# DSPCONN_12-15.net
KiCad netlist of a schematic drawn in Altium Designer
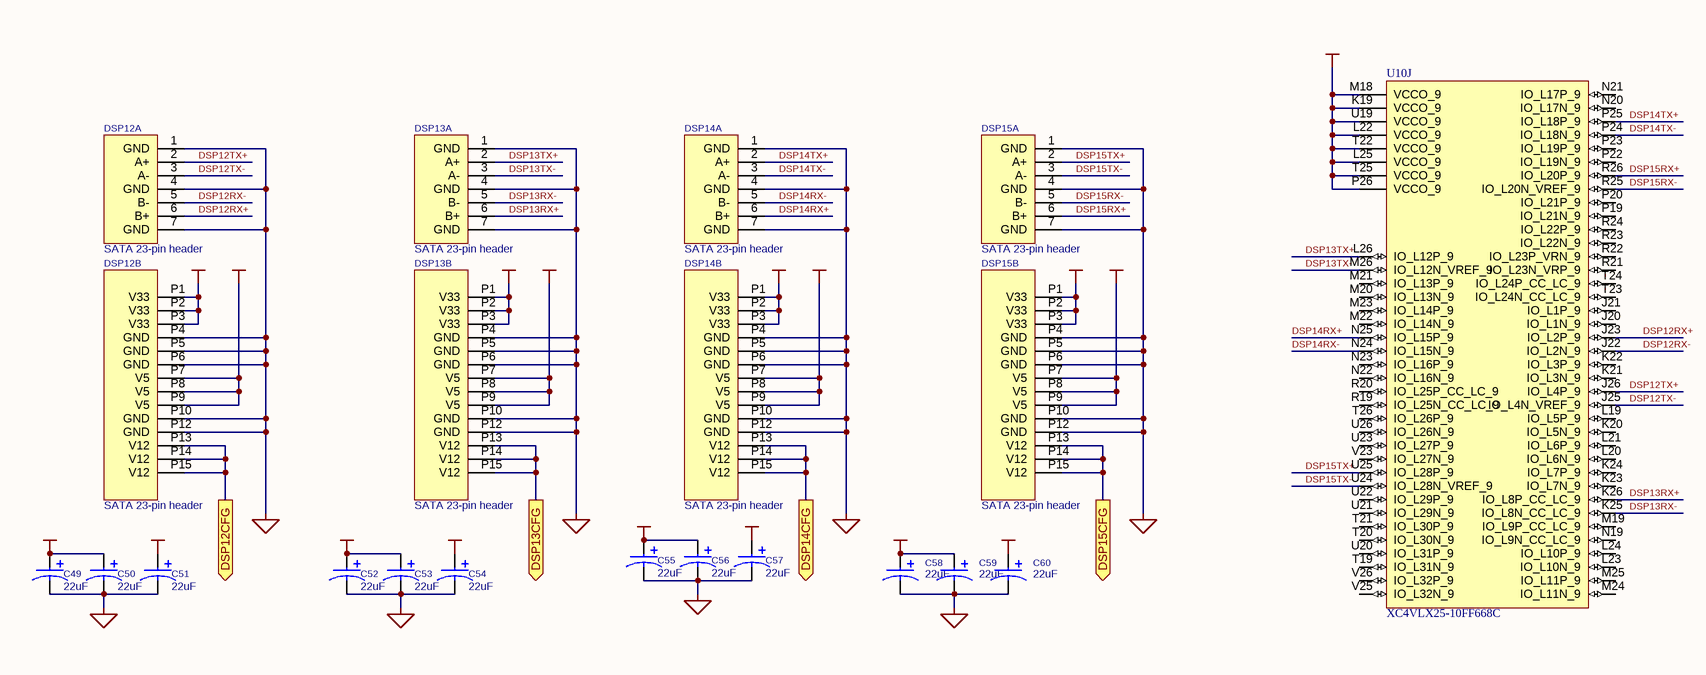
[diagram p0: DSPCONN.12-15.SCHDOC]

(export (version "E")
  (design (tool "Eeschema 10.0.6"))
  (components
    (comp (ref "C49")
      (value "22uF")
      (footprint "6032")
      (description "Standard Capacitor")
      (fields (field (name "Comment") "POLCAP2"))
      (libsource (lib "parts") (part "POLCAP2"))
    )
    (comp (ref "C50")
      (value "22uF")
      (footprint "6032")
      (description "Standard Capacitor")
      (fields (field (name "Comment") "POLCAP2"))
      (libsource (lib "parts") (part "POLCAP2"))
    )
    (comp (ref "C51")
      (value "22uF")
      (footprint "6032")
      (description "Standard Capacitor")
      (fields (field (name "Comment") "POLCAP2"))
      (libsource (lib "parts") (part "POLCAP2"))
    )
    (comp (ref "C52")
      (value "22uF")
      (footprint "6032")
      (description "Standard Capacitor")
      (fields (field (name "Comment") "POLCAP2"))
      (libsource (lib "parts") (part "POLCAP2"))
    )
    (comp (ref "C53")
      (value "22uF")
      (footprint "6032")
      (description "Standard Capacitor")
      (fields (field (name "Comment") "POLCAP2"))
      (libsource (lib "parts") (part "POLCAP2"))
    )
    (comp (ref "C54")
      (value "22uF")
      (footprint "6032")
      (description "Standard Capacitor")
      (fields (field (name "Comment") "POLCAP2"))
      (libsource (lib "parts") (part "POLCAP2"))
    )
    (comp (ref "C55")
      (value "22uF")
      (footprint "6032")
      (description "Standard Capacitor")
      (fields (field (name "Comment") "POLCAP2"))
      (libsource (lib "parts") (part "POLCAP2"))
    )
    (comp (ref "C56")
      (value "22uF")
      (footprint "6032")
      (description "Standard Capacitor")
      (fields (field (name "Comment") "POLCAP2"))
      (libsource (lib "parts") (part "POLCAP2"))
    )
    (comp (ref "C57")
      (value "22uF")
      (footprint "6032")
      (description "Standard Capacitor")
      (fields (field (name "Comment") "POLCAP2"))
      (libsource (lib "parts") (part "POLCAP2"))
    )
    (comp (ref "C58")
      (value "22uF")
      (footprint "6032")
      (description "Standard Capacitor")
      (fields (field (name "Comment") "POLCAP2"))
      (libsource (lib "parts") (part "POLCAP2"))
    )
    (comp (ref "C59")
      (value "22uF")
      (footprint "6032")
      (description "Standard Capacitor")
      (fields (field (name "Comment") "POLCAP2"))
      (libsource (lib "parts") (part "POLCAP2"))
    )
    (comp (ref "C60")
      (value "22uF")
      (footprint "6032")
      (description "Standard Capacitor")
      (fields (field (name "Comment") "POLCAP2"))
      (libsource (lib "parts") (part "POLCAP2"))
    )
    (comp (ref "DSP12")
      (value "SATA 23-pin header")
      (footprint "MOLEX 87713-1001")
      (libsource (lib "parts") (part "SATA-23"))
    )
    (comp (ref "DSP13")
      (value "SATA 23-pin header")
      (footprint "MOLEX 87713-1001")
      (libsource (lib "parts") (part "SATA-23"))
    )
    (comp (ref "DSP14")
      (value "SATA 23-pin header")
      (footprint "MOLEX 87713-1001")
      (libsource (lib "parts") (part "SATA-23"))
    )
    (comp (ref "DSP15")
      (value "SATA 23-pin header")
      (footprint "MOLEX 87713-1001")
      (libsource (lib "parts") (part "SATA-23"))
    )
    (comp (ref "U10")
      (value "XC4VLX25-10FF668C")
      (footprint "Xilinx FF668")
      (description "Xilinx Virtex-4")
      (libsource (lib "parts") (part "XC4VLX25-10FF668C"))
    )
  )
  (nets
    (net (code "1") (name "+2.5VCC") (class "Default")
      (node (ref "U10") (pin "K19") (pinfunction "VCCO_9_K19") (pintype "power_in"))
      (node (ref "U10") (pin "L22") (pinfunction "VCCO_9_L22") (pintype "power_in"))
      (node (ref "U10") (pin "L25") (pinfunction "VCCO_9_L25") (pintype "power_in"))
      (node (ref "U10") (pin "M18") (pinfunction "VCCO_9_M18") (pintype "power_in"))
      (node (ref "U10") (pin "P26") (pinfunction "VCCO_9_P26") (pintype "power_in"))
      (node (ref "U10") (pin "T22") (pinfunction "VCCO_9_T22") (pintype "power_in"))
      (node (ref "U10") (pin "T25") (pinfunction "VCCO_9_T25") (pintype "power_in"))
      (node (ref "U10") (pin "U19") (pinfunction "VCCO_9_U19") (pintype "power_in"))
    )
    (net (code "2") (name "+5VCC") (class "Default")
      (node (ref "C51") (pin "1") (pintype "passive"))
      (node (ref "C54") (pin "1") (pintype "passive"))
      (node (ref "C57") (pin "1") (pintype "passive"))
      (node (ref "C60") (pin "1") (pintype "passive"))
      (node (ref "DSP12") (pin "P7") (pinfunction "V5_P7") (pintype "passive"))
      (node (ref "DSP12") (pin "P8") (pinfunction "V5_P8") (pintype "passive"))
      (node (ref "DSP12") (pin "P9") (pinfunction "V5_P9") (pintype "passive"))
      (node (ref "DSP13") (pin "P7") (pinfunction "V5_P7") (pintype "passive"))
      (node (ref "DSP13") (pin "P8") (pinfunction "V5_P8") (pintype "passive"))
      (node (ref "DSP13") (pin "P9") (pinfunction "V5_P9") (pintype "passive"))
      (node (ref "DSP14") (pin "P7") (pinfunction "V5_P7") (pintype "passive"))
      (node (ref "DSP14") (pin "P8") (pinfunction "V5_P8") (pintype "passive"))
      (node (ref "DSP14") (pin "P9") (pinfunction "V5_P9") (pintype "passive"))
      (node (ref "DSP15") (pin "P7") (pinfunction "V5_P7") (pintype "passive"))
      (node (ref "DSP15") (pin "P8") (pinfunction "V5_P8") (pintype "passive"))
      (node (ref "DSP15") (pin "P9") (pinfunction "V5_P9") (pintype "passive"))
    )
    (net (code "3") (name "/DSP12CFG") (class "Default")
      (node (ref "DSP12") (pin "P13") (pinfunction "V12_P13") (pintype "passive"))
      (node (ref "DSP12") (pin "P14") (pinfunction "V12_P14") (pintype "passive"))
      (node (ref "DSP12") (pin "P15") (pinfunction "V12_P15") (pintype "passive"))
    )
    (net (code "4") (name "/DSP12RX+") (class "Default")
      (node (ref "DSP12") (pin "6") (pinfunction "B+_6") (pintype "passive"))
      (node (ref "U10") (pin "J23") (pinfunction "IO_L2P_9_J23") (pintype "bidirectional"))
    )
    (net (code "5") (name "/DSP12RX-") (class "Default")
      (node (ref "DSP12") (pin "5") (pinfunction "B-_5") (pintype "passive"))
      (node (ref "U10") (pin "J22") (pinfunction "IO_L2N_9_J22") (pintype "bidirectional"))
    )
    (net (code "6") (name "/DSP12TX+") (class "Default")
      (node (ref "DSP12") (pin "2") (pinfunction "A+_2") (pintype "passive"))
      (node (ref "U10") (pin "J26") (pinfunction "IO_L4P_9_J26") (pintype "bidirectional"))
    )
    (net (code "7") (name "/DSP12TX-") (class "Default")
      (node (ref "DSP12") (pin "3") (pinfunction "A-_3") (pintype "passive"))
      (node (ref "U10") (pin "J25") (pinfunction "IO_L4N_VREF_9_J25") (pintype "bidirectional"))
    )
    (net (code "8") (name "/DSP13CFG") (class "Default")
      (node (ref "DSP13") (pin "P13") (pinfunction "V12_P13") (pintype "passive"))
      (node (ref "DSP13") (pin "P14") (pinfunction "V12_P14") (pintype "passive"))
      (node (ref "DSP13") (pin "P15") (pinfunction "V12_P15") (pintype "passive"))
    )
    (net (code "9") (name "/DSP13RX+") (class "Default")
      (node (ref "DSP13") (pin "6") (pinfunction "B+_6") (pintype "passive"))
      (node (ref "U10") (pin "K26") (pinfunction "IO_L8P_CC_LC_9_K26") (pintype "bidirectional"))
    )
    (net (code "10") (name "/DSP13RX-") (class "Default")
      (node (ref "DSP13") (pin "5") (pinfunction "B-_5") (pintype "passive"))
      (node (ref "U10") (pin "K25") (pinfunction "IO_L8N_CC_LC_9_K25") (pintype "bidirectional"))
    )
    (net (code "11") (name "/DSP13TX+") (class "Default")
      (node (ref "DSP13") (pin "2") (pinfunction "A+_2") (pintype "passive"))
      (node (ref "U10") (pin "L26") (pinfunction "IO_L12P_9_L26") (pintype "bidirectional"))
    )
    (net (code "12") (name "/DSP13TX-") (class "Default")
      (node (ref "DSP13") (pin "3") (pinfunction "A-_3") (pintype "passive"))
      (node (ref "U10") (pin "M26") (pinfunction "IO_L12N_VREF_9_M26") (pintype "bidirectional"))
    )
    (net (code "13") (name "/DSP14CFG") (class "Default")
      (node (ref "DSP14") (pin "P13") (pinfunction "V12_P13") (pintype "passive"))
      (node (ref "DSP14") (pin "P14") (pinfunction "V12_P14") (pintype "passive"))
      (node (ref "DSP14") (pin "P15") (pinfunction "V12_P15") (pintype "passive"))
    )
    (net (code "14") (name "/DSP14RX+") (class "Default")
      (node (ref "DSP14") (pin "6") (pinfunction "B+_6") (pintype "passive"))
      (node (ref "U10") (pin "N25") (pinfunction "IO_L15P_9_N25") (pintype "bidirectional"))
    )
    (net (code "15") (name "/DSP14RX-") (class "Default")
      (node (ref "DSP14") (pin "5") (pinfunction "B-_5") (pintype "passive"))
      (node (ref "U10") (pin "N24") (pinfunction "IO_L15N_9_N24") (pintype "bidirectional"))
    )
    (net (code "16") (name "/DSP14TX+") (class "Default")
      (node (ref "DSP14") (pin "2") (pinfunction "A+_2") (pintype "passive"))
      (node (ref "U10") (pin "P25") (pinfunction "IO_L18P_9_P25") (pintype "bidirectional"))
    )
    (net (code "17") (name "/DSP14TX-") (class "Default")
      (node (ref "DSP14") (pin "3") (pinfunction "A-_3") (pintype "passive"))
      (node (ref "U10") (pin "P24") (pinfunction "IO_L18N_9_P24") (pintype "bidirectional"))
    )
    (net (code "18") (name "/DSP15CFG") (class "Default")
      (node (ref "DSP15") (pin "P13") (pinfunction "V12_P13") (pintype "passive"))
      (node (ref "DSP15") (pin "P14") (pinfunction "V12_P14") (pintype "passive"))
      (node (ref "DSP15") (pin "P15") (pinfunction "V12_P15") (pintype "passive"))
    )
    (net (code "19") (name "/DSP15RX+") (class "Default")
      (node (ref "DSP15") (pin "6") (pinfunction "B+_6") (pintype "passive"))
      (node (ref "U10") (pin "R26") (pinfunction "IO_L20P_9_R26") (pintype "bidirectional"))
    )
    (net (code "20") (name "/DSP15RX-") (class "Default")
      (node (ref "DSP15") (pin "5") (pinfunction "B-_5") (pintype "passive"))
      (node (ref "U10") (pin "R25") (pinfunction "IO_L20N_VREF_9_R25") (pintype "bidirectional"))
    )
    (net (code "21") (name "/DSP15TX+") (class "Default")
      (node (ref "DSP15") (pin "2") (pinfunction "A+_2") (pintype "passive"))
      (node (ref "U10") (pin "U25") (pinfunction "IO_L28P_9_U25") (pintype "bidirectional"))
    )
    (net (code "22") (name "/DSP15TX-") (class "Default")
      (node (ref "DSP15") (pin "3") (pinfunction "A-_3") (pintype "passive"))
      (node (ref "U10") (pin "U24") (pinfunction "IO_L28N_VREF_9_U24") (pintype "bidirectional"))
    )
    (net (code "23") (name "GND") (class "Default")
      (node (ref "C49") (pin "2") (pintype "passive"))
      (node (ref "C50") (pin "2") (pintype "passive"))
      (node (ref "C51") (pin "2") (pintype "passive"))
      (node (ref "C52") (pin "2") (pintype "passive"))
      (node (ref "C53") (pin "2") (pintype "passive"))
      (node (ref "C54") (pin "2") (pintype "passive"))
      (node (ref "C55") (pin "2") (pintype "passive"))
      (node (ref "C56") (pin "2") (pintype "passive"))
      (node (ref "C57") (pin "2") (pintype "passive"))
      (node (ref "C58") (pin "2") (pintype "passive"))
      (node (ref "C59") (pin "2") (pintype "passive"))
      (node (ref "C60") (pin "2") (pintype "passive"))
      (node (ref "DSP12") (pin "1") (pinfunction "GND_1") (pintype "passive"))
      (node (ref "DSP12") (pin "4") (pinfunction "GND_4") (pintype "passive"))
      (node (ref "DSP12") (pin "7") (pinfunction "GND_7") (pintype "passive"))
      (node (ref "DSP12") (pin "P10") (pinfunction "GND_P10") (pintype "passive"))
      (node (ref "DSP12") (pin "P12") (pinfunction "GND_P12") (pintype "passive"))
      (node (ref "DSP12") (pin "P4") (pinfunction "GND_P4") (pintype "passive"))
      (node (ref "DSP12") (pin "P5") (pinfunction "GND_P5") (pintype "passive"))
      (node (ref "DSP12") (pin "P6") (pinfunction "GND_P6") (pintype "passive"))
      (node (ref "DSP13") (pin "1") (pinfunction "GND_1") (pintype "passive"))
      (node (ref "DSP13") (pin "4") (pinfunction "GND_4") (pintype "passive"))
      (node (ref "DSP13") (pin "7") (pinfunction "GND_7") (pintype "passive"))
      (node (ref "DSP13") (pin "P10") (pinfunction "GND_P10") (pintype "passive"))
      (node (ref "DSP13") (pin "P12") (pinfunction "GND_P12") (pintype "passive"))
      (node (ref "DSP13") (pin "P4") (pinfunction "GND_P4") (pintype "passive"))
      (node (ref "DSP13") (pin "P5") (pinfunction "GND_P5") (pintype "passive"))
      (node (ref "DSP13") (pin "P6") (pinfunction "GND_P6") (pintype "passive"))
      (node (ref "DSP14") (pin "1") (pinfunction "GND_1") (pintype "passive"))
      (node (ref "DSP14") (pin "4") (pinfunction "GND_4") (pintype "passive"))
      (node (ref "DSP14") (pin "7") (pinfunction "GND_7") (pintype "passive"))
      (node (ref "DSP14") (pin "P10") (pinfunction "GND_P10") (pintype "passive"))
      (node (ref "DSP14") (pin "P12") (pinfunction "GND_P12") (pintype "passive"))
      (node (ref "DSP14") (pin "P4") (pinfunction "GND_P4") (pintype "passive"))
      (node (ref "DSP14") (pin "P5") (pinfunction "GND_P5") (pintype "passive"))
      (node (ref "DSP14") (pin "P6") (pinfunction "GND_P6") (pintype "passive"))
      (node (ref "DSP15") (pin "1") (pinfunction "GND_1") (pintype "passive"))
      (node (ref "DSP15") (pin "4") (pinfunction "GND_4") (pintype "passive"))
      (node (ref "DSP15") (pin "7") (pinfunction "GND_7") (pintype "passive"))
      (node (ref "DSP15") (pin "P10") (pinfunction "GND_P10") (pintype "passive"))
      (node (ref "DSP15") (pin "P12") (pinfunction "GND_P12") (pintype "passive"))
      (node (ref "DSP15") (pin "P4") (pinfunction "GND_P4") (pintype "passive"))
      (node (ref "DSP15") (pin "P5") (pinfunction "GND_P5") (pintype "passive"))
      (node (ref "DSP15") (pin "P6") (pinfunction "GND_P6") (pintype "passive"))
    )
    (net (code "24") (name "VCC2") (class "Default")
      (node (ref "C49") (pin "1") (pintype "passive"))
      (node (ref "C50") (pin "1") (pintype "passive"))
      (node (ref "C52") (pin "1") (pintype "passive"))
      (node (ref "C53") (pin "1") (pintype "passive"))
      (node (ref "C55") (pin "1") (pintype "passive"))
      (node (ref "C56") (pin "1") (pintype "passive"))
      (node (ref "C58") (pin "1") (pintype "passive"))
      (node (ref "C59") (pin "1") (pintype "passive"))
      (node (ref "DSP12") (pin "P1") (pinfunction "V33_P1") (pintype "passive"))
      (node (ref "DSP12") (pin "P2") (pinfunction "V33_P2") (pintype "passive"))
      (node (ref "DSP12") (pin "P3") (pinfunction "V33_P3") (pintype "passive"))
      (node (ref "DSP13") (pin "P1") (pinfunction "V33_P1") (pintype "passive"))
      (node (ref "DSP13") (pin "P2") (pinfunction "V33_P2") (pintype "passive"))
      (node (ref "DSP13") (pin "P3") (pinfunction "V33_P3") (pintype "passive"))
      (node (ref "DSP14") (pin "P1") (pinfunction "V33_P1") (pintype "passive"))
      (node (ref "DSP14") (pin "P2") (pinfunction "V33_P2") (pintype "passive"))
      (node (ref "DSP14") (pin "P3") (pinfunction "V33_P3") (pintype "passive"))
      (node (ref "DSP15") (pin "P1") (pinfunction "V33_P1") (pintype "passive"))
      (node (ref "DSP15") (pin "P2") (pinfunction "V33_P2") (pintype "passive"))
      (node (ref "DSP15") (pin "P3") (pinfunction "V33_P3") (pintype "passive"))
    )
    (net (code "25") (name "unconnected-(U10J-IO_L1N_9-PadJ20)") (class "Default")
      (node (ref "U10") (pin "J20") (pinfunction "IO_L1N_9_J20") (pintype "bidirectional"))
    )
    (net (code "26") (name "unconnected-(U10J-IO_L1P_9-PadJ21)") (class "Default")
      (node (ref "U10") (pin "J21") (pinfunction "IO_L1P_9_J21") (pintype "bidirectional"))
    )
    (net (code "27") (name "unconnected-(U10J-IO_L3N_9-PadK21)") (class "Default")
      (node (ref "U10") (pin "K21") (pinfunction "IO_L3N_9_K21") (pintype "bidirectional"))
    )
    (net (code "28") (name "unconnected-(U10J-IO_L3P_9-PadK22)") (class "Default")
      (node (ref "U10") (pin "K22") (pinfunction "IO_L3P_9_K22") (pintype "bidirectional"))
    )
    (net (code "29") (name "unconnected-(U10J-IO_L5N_9-PadK20)") (class "Default")
      (node (ref "U10") (pin "K20") (pinfunction "IO_L5N_9_K20") (pintype "bidirectional"))
    )
    (net (code "30") (name "unconnected-(U10J-IO_L5P_9-PadL19)") (class "Default")
      (node (ref "U10") (pin "L19") (pinfunction "IO_L5P_9_L19") (pintype "bidirectional"))
    )
    (net (code "31") (name "unconnected-(U10J-IO_L6N_9-PadL20)") (class "Default")
      (node (ref "U10") (pin "L20") (pinfunction "IO_L6N_9_L20") (pintype "bidirectional"))
    )
    (net (code "32") (name "unconnected-(U10J-IO_L6P_9-PadL21)") (class "Default")
      (node (ref "U10") (pin "L21") (pinfunction "IO_L6P_9_L21") (pintype "bidirectional"))
    )
    (net (code "33") (name "unconnected-(U10J-IO_L7N_9-PadK23)") (class "Default")
      (node (ref "U10") (pin "K23") (pinfunction "IO_L7N_9_K23") (pintype "bidirectional"))
    )
    (net (code "34") (name "unconnected-(U10J-IO_L7P_9-PadK24)") (class "Default")
      (node (ref "U10") (pin "K24") (pinfunction "IO_L7P_9_K24") (pintype "bidirectional"))
    )
    (net (code "35") (name "unconnected-(U10J-IO_L9N_CC_LC_9-PadN19)") (class "Default")
      (node (ref "U10") (pin "N19") (pinfunction "IO_L9N_CC_LC_9_N19") (pintype "bidirectional"))
    )
    (net (code "36") (name "unconnected-(U10J-IO_L9P_CC_LC_9-PadM19)") (class "Default")
      (node (ref "U10") (pin "M19") (pinfunction "IO_L9P_CC_LC_9_M19") (pintype "bidirectional"))
    )
    (net (code "37") (name "unconnected-(U10J-IO_L10N_9-PadL23)") (class "Default")
      (node (ref "U10") (pin "L23") (pinfunction "IO_L10N_9_L23") (pintype "bidirectional"))
    )
    (net (code "38") (name "unconnected-(U10J-IO_L10P_9-PadL24)") (class "Default")
      (node (ref "U10") (pin "L24") (pinfunction "IO_L10P_9_L24") (pintype "bidirectional"))
    )
    (net (code "39") (name "unconnected-(U10J-IO_L11N_9-PadM24)") (class "Default")
      (node (ref "U10") (pin "M24") (pinfunction "IO_L11N_9_M24") (pintype "bidirectional"))
    )
    (net (code "40") (name "unconnected-(U10J-IO_L11P_9-PadM25)") (class "Default")
      (node (ref "U10") (pin "M25") (pinfunction "IO_L11P_9_M25") (pintype "bidirectional"))
    )
    (net (code "41") (name "unconnected-(U10J-IO_L13N_9-PadM20)") (class "Default")
      (node (ref "U10") (pin "M20") (pinfunction "IO_L13N_9_M20") (pintype "bidirectional"))
    )
    (net (code "42") (name "unconnected-(U10J-IO_L13P_9-PadM21)") (class "Default")
      (node (ref "U10") (pin "M21") (pinfunction "IO_L13P_9_M21") (pintype "bidirectional"))
    )
    (net (code "43") (name "unconnected-(U10J-IO_L14N_9-PadM22)") (class "Default")
      (node (ref "U10") (pin "M22") (pinfunction "IO_L14N_9_M22") (pintype "bidirectional"))
    )
    (net (code "44") (name "unconnected-(U10J-IO_L14P_9-PadM23)") (class "Default")
      (node (ref "U10") (pin "M23") (pinfunction "IO_L14P_9_M23") (pintype "bidirectional"))
    )
    (net (code "45") (name "unconnected-(U10J-IO_L16N_9-PadN22)") (class "Default")
      (node (ref "U10") (pin "N22") (pinfunction "IO_L16N_9_N22") (pintype "bidirectional"))
    )
    (net (code "46") (name "unconnected-(U10J-IO_L16P_9-PadN23)") (class "Default")
      (node (ref "U10") (pin "N23") (pinfunction "IO_L16P_9_N23") (pintype "bidirectional"))
    )
    (net (code "47") (name "unconnected-(U10J-IO_L17N_9-PadN20)") (class "Default")
      (node (ref "U10") (pin "N20") (pinfunction "IO_L17N_9_N20") (pintype "bidirectional"))
    )
    (net (code "48") (name "unconnected-(U10J-IO_L17P_9-PadN21)") (class "Default")
      (node (ref "U10") (pin "N21") (pinfunction "IO_L17P_9_N21") (pintype "bidirectional"))
    )
    (net (code "49") (name "unconnected-(U10J-IO_L19N_9-PadP22)") (class "Default")
      (node (ref "U10") (pin "P22") (pinfunction "IO_L19N_9_P22") (pintype "bidirectional"))
    )
    (net (code "50") (name "unconnected-(U10J-IO_L19P_9-PadP23)") (class "Default")
      (node (ref "U10") (pin "P23") (pinfunction "IO_L19P_9_P23") (pintype "bidirectional"))
    )
    (net (code "51") (name "unconnected-(U10J-IO_L21N_9-PadP19)") (class "Default")
      (node (ref "U10") (pin "P19") (pinfunction "IO_L21N_9_P19") (pintype "bidirectional"))
    )
    (net (code "52") (name "unconnected-(U10J-IO_L21P_9-PadP20)") (class "Default")
      (node (ref "U10") (pin "P20") (pinfunction "IO_L21P_9_P20") (pintype "bidirectional"))
    )
    (net (code "53") (name "unconnected-(U10J-IO_L22N_9-PadR23)") (class "Default")
      (node (ref "U10") (pin "R23") (pinfunction "IO_L22N_9_R23") (pintype "bidirectional"))
    )
    (net (code "54") (name "unconnected-(U10J-IO_L22P_9-PadR24)") (class "Default")
      (node (ref "U10") (pin "R24") (pinfunction "IO_L22P_9_R24") (pintype "bidirectional"))
    )
    (net (code "55") (name "unconnected-(U10J-IO_L23N_VRP_9-PadR21)") (class "Default")
      (node (ref "U10") (pin "R21") (pinfunction "IO_L23N_VRP_9_R21") (pintype "bidirectional"))
    )
    (net (code "56") (name "unconnected-(U10J-IO_L23P_VRN_9-PadR22)") (class "Default")
      (node (ref "U10") (pin "R22") (pinfunction "IO_L23P_VRN_9_R22") (pintype "bidirectional"))
    )
    (net (code "57") (name "unconnected-(U10J-IO_L24N_CC_LC_9-PadT23)") (class "Default")
      (node (ref "U10") (pin "T23") (pinfunction "IO_L24N_CC_LC_9_T23") (pintype "bidirectional"))
    )
    (net (code "58") (name "unconnected-(U10J-IO_L24P_CC_LC_9-PadT24)") (class "Default")
      (node (ref "U10") (pin "T24") (pinfunction "IO_L24P_CC_LC_9_T24") (pintype "bidirectional"))
    )
    (net (code "59") (name "unconnected-(U10J-IO_L25N_CC_LC_9-PadR19)") (class "Default")
      (node (ref "U10") (pin "R19") (pinfunction "IO_L25N_CC_LC_9_R19") (pintype "bidirectional"))
    )
    (net (code "60") (name "unconnected-(U10J-IO_L25P_CC_LC_9-PadR20)") (class "Default")
      (node (ref "U10") (pin "R20") (pinfunction "IO_L25P_CC_LC_9_R20") (pintype "bidirectional"))
    )
    (net (code "61") (name "unconnected-(U10J-IO_L26N_9-PadU26)") (class "Default")
      (node (ref "U10") (pin "U26") (pinfunction "IO_L26N_9_U26") (pintype "bidirectional"))
    )
    (net (code "62") (name "unconnected-(U10J-IO_L26P_9-PadT26)") (class "Default")
      (node (ref "U10") (pin "T26") (pinfunction "IO_L26P_9_T26") (pintype "bidirectional"))
    )
    (net (code "63") (name "unconnected-(U10J-IO_L27N_9-PadV23)") (class "Default")
      (node (ref "U10") (pin "V23") (pinfunction "IO_L27N_9_V23") (pintype "bidirectional"))
    )
    (net (code "64") (name "unconnected-(U10J-IO_L27P_9-PadU23)") (class "Default")
      (node (ref "U10") (pin "U23") (pinfunction "IO_L27P_9_U23") (pintype "bidirectional"))
    )
    (net (code "65") (name "unconnected-(U10J-IO_L29N_9-PadU21)") (class "Default")
      (node (ref "U10") (pin "U21") (pinfunction "IO_L29N_9_U21") (pintype "bidirectional"))
    )
    (net (code "66") (name "unconnected-(U10J-IO_L29P_9-PadU22)") (class "Default")
      (node (ref "U10") (pin "U22") (pinfunction "IO_L29P_9_U22") (pintype "bidirectional"))
    )
    (net (code "67") (name "unconnected-(U10J-IO_L30N_9-PadT20)") (class "Default")
      (node (ref "U10") (pin "T20") (pinfunction "IO_L30N_9_T20") (pintype "bidirectional"))
    )
    (net (code "68") (name "unconnected-(U10J-IO_L30P_9-PadT21)") (class "Default")
      (node (ref "U10") (pin "T21") (pinfunction "IO_L30P_9_T21") (pintype "bidirectional"))
    )
    (net (code "69") (name "unconnected-(U10J-IO_L31N_9-PadT19)") (class "Default")
      (node (ref "U10") (pin "T19") (pinfunction "IO_L31N_9_T19") (pintype "bidirectional"))
    )
    (net (code "70") (name "unconnected-(U10J-IO_L31P_9-PadU20)") (class "Default")
      (node (ref "U10") (pin "U20") (pinfunction "IO_L31P_9_U20") (pintype "bidirectional"))
    )
    (net (code "71") (name "unconnected-(U10J-IO_L32N_9-PadV25)") (class "Default")
      (node (ref "U10") (pin "V25") (pinfunction "IO_L32N_9_V25") (pintype "bidirectional"))
    )
    (net (code "72") (name "unconnected-(U10J-IO_L32P_9-PadV26)") (class "Default")
      (node (ref "U10") (pin "V26") (pinfunction "IO_L32P_9_V26") (pintype "bidirectional"))
    )
  )
)
